# VCF-LM324-Mono.net
KiCad netlist of a schematic drawn in EAGLE
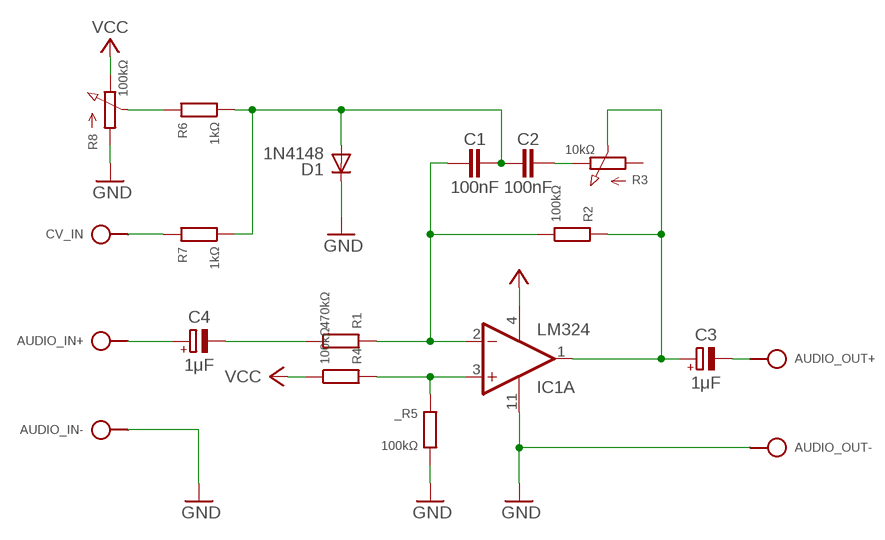
[diagram p0: schematic, sheet 1]

(export (version "E")
  (design (tool "Eeschema 10.0.6"))
  (components
    (comp (ref "AUDIO_IN+")
      (value "AUDIO_IN")
      (footprint "eagle-import:SPAD")
      (libsource (lib "eagle-import") (part "SPAD"))
    )
    (comp (ref "AUDIO_IN-")
      (value "SPAD")
      (footprint "eagle-import:SPAD")
      (libsource (lib "eagle-import") (part "SPAD"))
    )
    (comp (ref "AUDIO_OUT+")
      (value "AUDIO_OUT")
      (footprint "eagle-import:SPAD")
      (libsource (lib "eagle-import") (part "SPAD"))
    )
    (comp (ref "AUDIO_OUT-")
      (value "SPAD")
      (footprint "eagle-import:SPAD")
      (libsource (lib "eagle-import") (part "SPAD"))
    )
    (comp (ref "C1")
      (value "100nF")
      (footprint "eagle-import:C050-024X044")
      (libsource (lib "eagle-import") (part "C050-024X044"))
    )
    (comp (ref "C2")
      (value "100nF")
      (footprint "eagle-import:C050-024X044")
      (libsource (lib "eagle-import") (part "C050-024X044"))
    )
    (comp (ref "C3")
      (value "1μF")
      (footprint "eagle-import:E2,5-3")
      (libsource (lib "eagle-import") (part "CPOLE2,5-3"))
    )
    (comp (ref "C4")
      (value "1μF")
      (footprint "eagle-import:E2,5-3")
      (libsource (lib "eagle-import") (part "CPOLE2,5-3"))
    )
    (comp (ref "CV_IN")
      (value "CV_IN")
      (footprint "eagle-import:SPAD")
      (libsource (lib "eagle-import") (part "SPAD"))
    )
    (comp (ref "D1")
      (value "1N4148")
      (footprint "eagle-import:DO34-7")
      (libsource (lib "eagle-import") (part "1N414834-7"))
    )
    (comp (ref "IC1")
      (value "LM324")
      (footprint "eagle-import:DIL14")
      (libsource (lib "eagle-import") (part "LM324N"))
    )
    (comp (ref "R1")
      (value "470kΩ")
      (footprint "eagle-import:0202_7")
      (libsource (lib "eagle-import") (part "R0202/7"))
    )
    (comp (ref "R2")
      (value "100kΩ")
      (footprint "eagle-import:0202V")
      (libsource (lib "eagle-import") (part "R0202V"))
    )
    (comp (ref "R3")
      (value "10kΩ")
      (footprint "eagle-import:POT-P5")
      (libsource (lib "eagle-import") (part "POT-P5"))
    )
    (comp (ref "R4")
      (value "100kΩ")
      (footprint "eagle-import:0202V")
      (libsource (lib "eagle-import") (part "R0202V"))
    )
    (comp (ref "R6")
      (value "1kΩ")
      (footprint "eagle-import:0202_10")
      (libsource (lib "eagle-import") (part "R0202/10"))
    )
    (comp (ref "R7")
      (value "1kΩ")
      (footprint "eagle-import:0202_7")
      (libsource (lib "eagle-import") (part "R0202/7"))
    )
    (comp (ref "R8")
      (value "100kΩ")
      (footprint "eagle-import:POT-P5")
      (libsource (lib "eagle-import") (part "POT-P5"))
    )
    (comp (ref "_R5")
      (value "100kΩ")
      (footprint "eagle-import:0202_7")
      (libsource (lib "eagle-import") (part "R0202/7"))
    )
  )
  (nets
    (net (code "1") (name "GND") (class "Default")
      (node (ref "AUDIO_IN-") (pin "1") (pinfunction "P$1_1") (pintype "bidirectional"))
      (node (ref "AUDIO_OUT-") (pin "1") (pinfunction "P$1_1") (pintype "bidirectional"))
      (node (ref "D1") (pin "C") (pinfunction "C_C") (pintype "passive"))
      (node (ref "IC1") (pin "11") (pinfunction "V-_11") (pintype "power_in"))
      (node (ref "R8") (pin "A") (pinfunction "A_A") (pintype "passive"))
      (node (ref "_R5") (pin "1") (pinfunction "1_1") (pintype "passive"))
    )
    (net (code "2") (name "Net-(AUDIO_IN+-P$1)") (class "Default")
      (node (ref "AUDIO_IN+") (pin "1") (pinfunction "P$1_1") (pintype "bidirectional"))
      (node (ref "C4") (pin "+") (pinfunction "+_+") (pintype "passive"))
    )
    (net (code "3") (name "Net-(AUDIO_OUT+-P$1)") (class "Default")
      (node (ref "AUDIO_OUT+") (pin "1") (pinfunction "P$1_1") (pintype "bidirectional"))
      (node (ref "C3") (pin "-") (pinfunction "-_-") (pintype "passive"))
    )
    (net (code "4") (name "Net-(C1-Pad2)") (class "Default")
      (node (ref "C1") (pin "2") (pinfunction "2_2") (pintype "passive"))
      (node (ref "C2") (pin "1") (pinfunction "1_1") (pintype "passive"))
      (node (ref "D1") (pin "A") (pinfunction "A_A") (pintype "passive"))
      (node (ref "R6") (pin "1") (pinfunction "1_1") (pintype "passive"))
      (node (ref "R7") (pin "1") (pinfunction "1_1") (pintype "passive"))
    )
    (net (code "5") (name "Net-(C2-Pad2)") (class "Default")
      (node (ref "C2") (pin "2") (pinfunction "2_2") (pintype "passive"))
      (node (ref "R3") (pin "E") (pinfunction "E_E") (pintype "passive"))
    )
    (net (code "6") (name "Net-(C4-Pad-)") (class "Default")
      (node (ref "C4") (pin "-") (pinfunction "-_-") (pintype "passive"))
      (node (ref "R1") (pin "1") (pinfunction "1_1") (pintype "passive"))
    )
    (net (code "7") (name "Net-(CV_IN-P$1)") (class "Default")
      (node (ref "CV_IN") (pin "1") (pinfunction "P$1_1") (pintype "bidirectional"))
      (node (ref "R7") (pin "2") (pinfunction "2_2") (pintype "passive"))
    )
    (net (code "8") (name "Net-(IC1A-+IN)") (class "Default")
      (node (ref "IC1") (pin "3") (pinfunction "+IN_3") (pintype "input"))
      (node (ref "R4") (pin "2") (pinfunction "2_2") (pintype "passive"))
      (node (ref "_R5") (pin "2") (pinfunction "2_2") (pintype "passive"))
    )
    (net (code "9") (name "Net-(IC1A--IN)") (class "Default")
      (node (ref "C1") (pin "1") (pinfunction "1_1") (pintype "passive"))
      (node (ref "IC1") (pin "2") (pinfunction "-IN_2") (pintype "input"))
      (node (ref "R1") (pin "2") (pinfunction "2_2") (pintype "passive"))
      (node (ref "R2") (pin "1") (pinfunction "1_1") (pintype "passive"))
    )
    (net (code "10") (name "Net-(IC1A-OUT)") (class "Default")
      (node (ref "C3") (pin "+") (pinfunction "+_+") (pintype "passive"))
      (node (ref "IC1") (pin "1") (pinfunction "OUT_1") (pintype "output"))
      (node (ref "R2") (pin "2") (pinfunction "2_2") (pintype "passive"))
      (node (ref "R3") (pin "S") (pinfunction "S_S") (pintype "passive"))
    )
    (net (code "11") (name "Net-(R6-Pad2)") (class "Default")
      (node (ref "R6") (pin "2") (pinfunction "2_2") (pintype "passive"))
      (node (ref "R8") (pin "S") (pinfunction "S_S") (pintype "passive"))
    )
    (net (code "12") (name "VCC") (class "Default")
      (node (ref "IC1") (pin "4") (pinfunction "V+_4") (pintype "power_in"))
      (node (ref "R4") (pin "1") (pinfunction "1_1") (pintype "passive"))
      (node (ref "R8") (pin "E") (pinfunction "E_E") (pintype "passive"))
    )
    (net (code "13") (name "unconnected-(R3-PadA)") (class "Default")
      (node (ref "R3") (pin "A") (pinfunction "A_A") (pintype "passive"))
    )
  )
)
